# SilovaCast.net
KiCad netlist of a schematic drawn in EAGLE
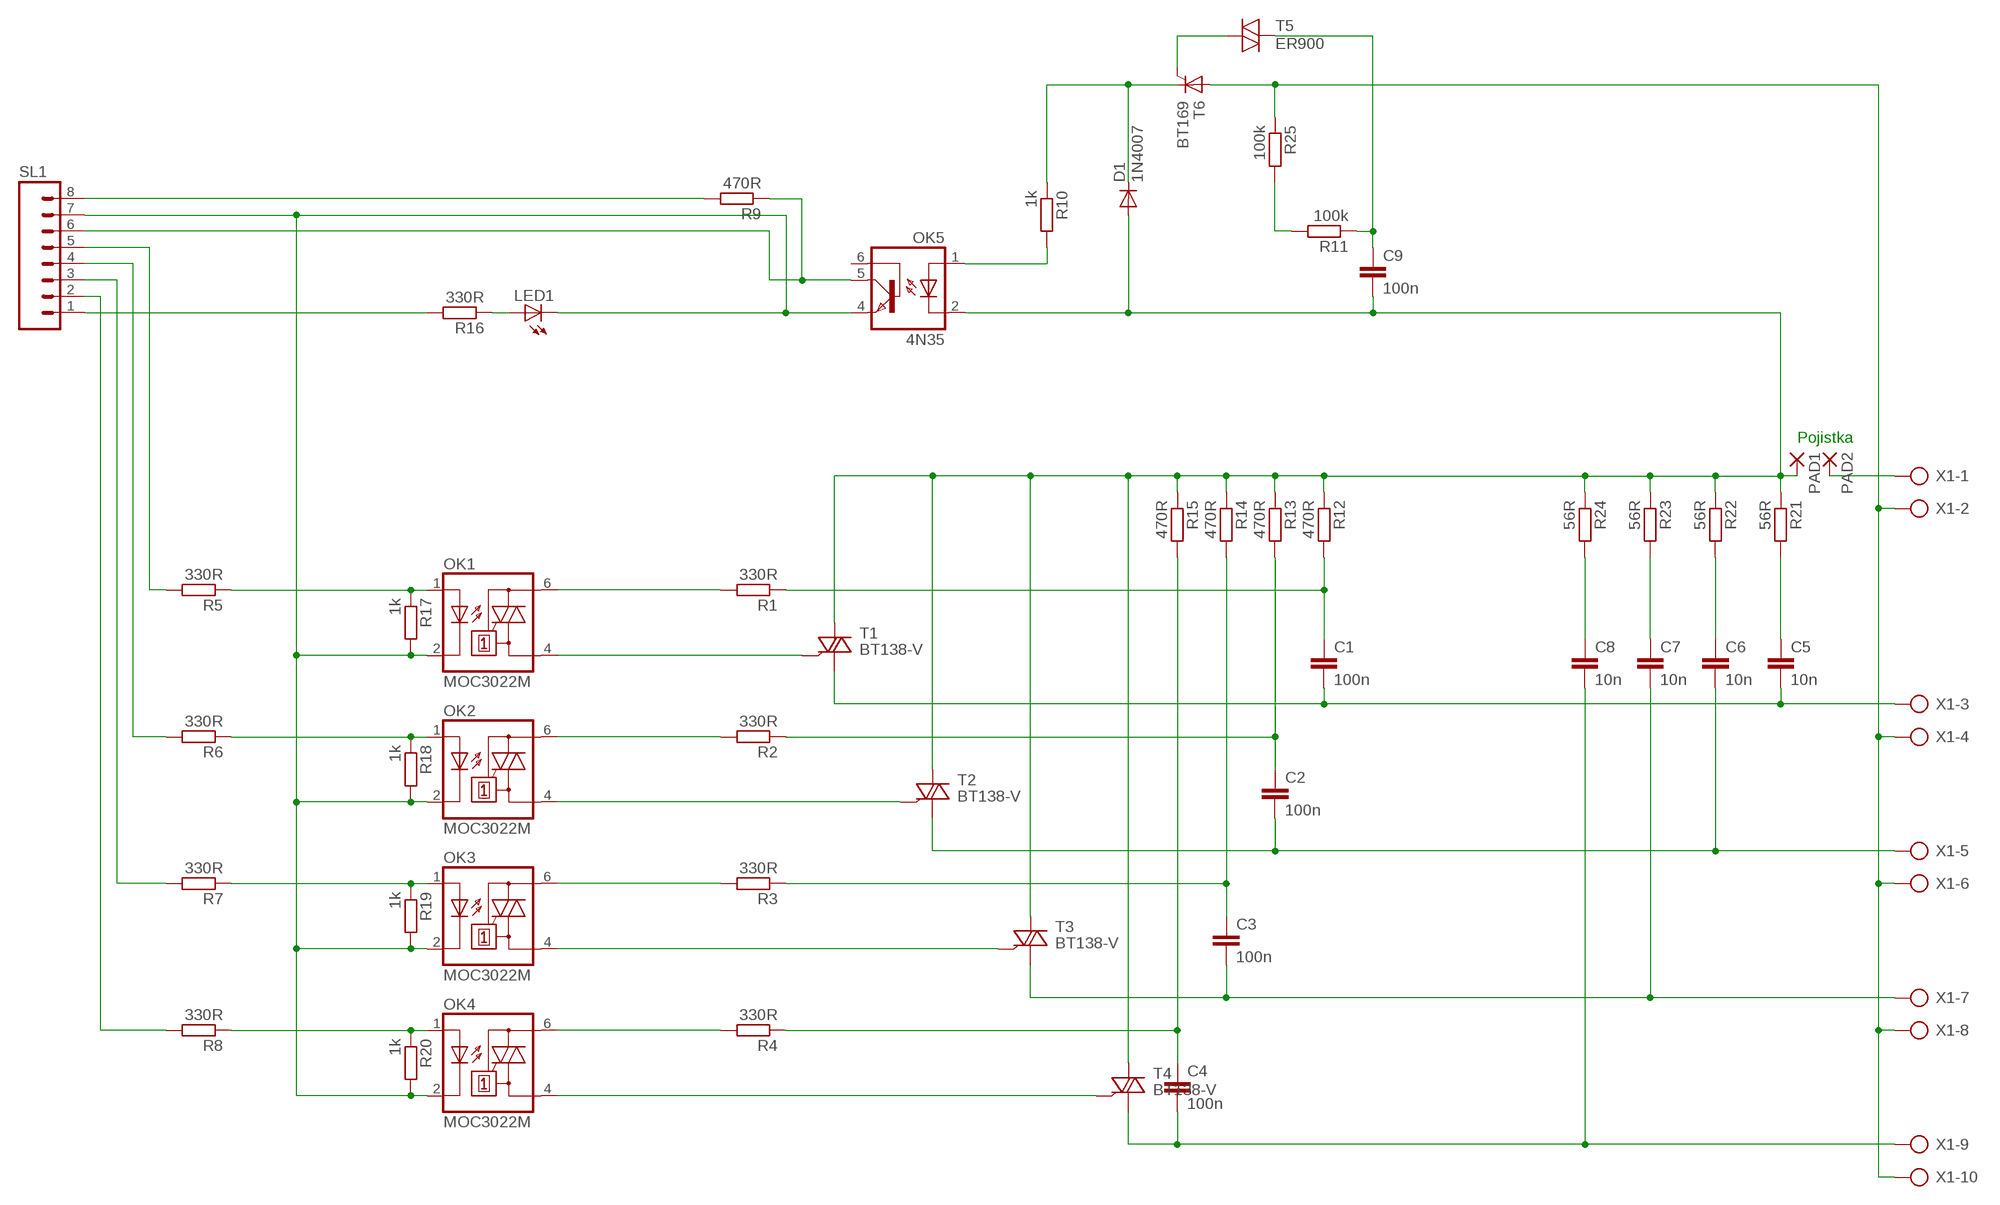
[diagram p0: schematic, sheet 1]

(export (version "E")
  (design (tool "Eeschema 10.0.6"))
  (components
    (comp (ref "C1")
      (value "100n")
      (footprint "eagle-import:C7.5B6")
      (libsource (lib "eagle-import") (part "C7.5/6"))
    )
    (comp (ref "C2")
      (value "100n")
      (footprint "eagle-import:C7.5B6")
      (libsource (lib "eagle-import") (part "C7.5/6"))
    )
    (comp (ref "C3")
      (value "100n")
      (footprint "eagle-import:C7.5B6")
      (libsource (lib "eagle-import") (part "C7.5/6"))
    )
    (comp (ref "C4")
      (value "100n")
      (footprint "eagle-import:C7.5B6")
      (libsource (lib "eagle-import") (part "C7.5/6"))
    )
    (comp (ref "C5")
      (value "10n")
      (footprint "eagle-import:C7.5B6")
      (libsource (lib "eagle-import") (part "C7.5/6"))
    )
    (comp (ref "C6")
      (value "10n")
      (footprint "eagle-import:C7.5B6")
      (libsource (lib "eagle-import") (part "C7.5/6"))
    )
    (comp (ref "C7")
      (value "10n")
      (footprint "eagle-import:C7.5B6")
      (libsource (lib "eagle-import") (part "C7.5/6"))
    )
    (comp (ref "C8")
      (value "10n")
      (footprint "eagle-import:C7.5B6")
      (libsource (lib "eagle-import") (part "C7.5/6"))
    )
    (comp (ref "C9")
      (value "100n")
      (footprint "eagle-import:C7.5B6")
      (libsource (lib "eagle-import") (part "C7.5/6"))
    )
    (comp (ref "D1")
      (value "1N4007")
      (footprint "eagle-import:DO41-10")
      (libsource (lib "eagle-import") (part "1N4004"))
    )
    (comp (ref "LED1")
      (value "LED5MM")
      (footprint "eagle-import:LED5MM")
      (libsource (lib "eagle-import") (part "LED5MM"))
    )
    (comp (ref "OK1")
      (value "MOC3022M")
      (footprint "eagle-import:DIL06")
      (fields (field (name "MF") "FAIRCHILD SEMICONDUCTOR") (field (name "MPN") "MOC3022-M"))
      (libsource (lib "eagle-import") (part "MOC30M22"))
    )
    (comp (ref "OK2")
      (value "MOC3022M")
      (footprint "eagle-import:DIL06")
      (fields (field (name "MF") "FAIRCHILD SEMICONDUCTOR") (field (name "MPN") "MOC3022-M"))
      (libsource (lib "eagle-import") (part "MOC30M22"))
    )
    (comp (ref "OK3")
      (value "MOC3022M")
      (footprint "eagle-import:DIL06")
      (fields (field (name "MF") "FAIRCHILD SEMICONDUCTOR") (field (name "MPN") "MOC3022-M"))
      (libsource (lib "eagle-import") (part "MOC30M22"))
    )
    (comp (ref "OK4")
      (value "MOC3022M")
      (footprint "eagle-import:DIL06")
      (fields (field (name "MF") "FAIRCHILD SEMICONDUCTOR") (field (name "MPN") "MOC3022-M"))
      (libsource (lib "eagle-import") (part "MOC30M22"))
    )
    (comp (ref "OK5")
      (value "4N35")
      (footprint "eagle-import:DIL06")
      (fields (field (name "MF") "FAIRCHILD SEMICONDUCTOR"))
      (libsource (lib "eagle-import") (part "4N35"))
    )
    (comp (ref "PAD1")
      (value "3,17/1,3")
      (footprint "eagle-import:3,17_1,3")
      (libsource (lib "eagle-import") (part "3,17/1,3"))
    )
    (comp (ref "PAD2")
      (value "3,17/1,3")
      (footprint "eagle-import:3,17_1,3")
      (libsource (lib "eagle-import") (part "3,17/1,3"))
    )
    (comp (ref "R1")
      (value "330R")
      (footprint "eagle-import:0207_12")
      (libsource (lib "eagle-import") (part "R-EU_0207/12"))
    )
    (comp (ref "R2")
      (value "330R")
      (footprint "eagle-import:0207_12")
      (libsource (lib "eagle-import") (part "R-EU_0207/12"))
    )
    (comp (ref "R3")
      (value "330R")
      (footprint "eagle-import:0207_12")
      (libsource (lib "eagle-import") (part "R-EU_0207/12"))
    )
    (comp (ref "R4")
      (value "330R")
      (footprint "eagle-import:0207_12")
      (libsource (lib "eagle-import") (part "R-EU_0207/12"))
    )
    (comp (ref "R5")
      (value "330R")
      (footprint "eagle-import:R0805")
      (libsource (lib "eagle-import") (part "R-EU_R0805"))
    )
    (comp (ref "R6")
      (value "330R")
      (footprint "eagle-import:R0805")
      (libsource (lib "eagle-import") (part "R-EU_R0805"))
    )
    (comp (ref "R7")
      (value "330R")
      (footprint "eagle-import:R0805")
      (libsource (lib "eagle-import") (part "R-EU_R0805"))
    )
    (comp (ref "R8")
      (value "330R")
      (footprint "eagle-import:R0805")
      (libsource (lib "eagle-import") (part "R-EU_R0805"))
    )
    (comp (ref "R9")
      (value "470R")
      (footprint "eagle-import:0207_12")
      (libsource (lib "eagle-import") (part "R-EU_0207/12"))
    )
    (comp (ref "R10")
      (value "1k")
      (footprint "eagle-import:0207_12")
      (libsource (lib "eagle-import") (part "R-EU_0207/12"))
    )
    (comp (ref "R11")
      (value "100k")
      (footprint "eagle-import:0207_12")
      (libsource (lib "eagle-import") (part "R-EU_0207/12"))
    )
    (comp (ref "R12")
      (value "470R")
      (footprint "eagle-import:0207_12")
      (libsource (lib "eagle-import") (part "R-EU_0207/12"))
    )
    (comp (ref "R13")
      (value "470R")
      (footprint "eagle-import:0207_12")
      (libsource (lib "eagle-import") (part "R-EU_0207/12"))
    )
    (comp (ref "R14")
      (value "470R")
      (footprint "eagle-import:0207_12")
      (libsource (lib "eagle-import") (part "R-EU_0207/12"))
    )
    (comp (ref "R15")
      (value "470R")
      (footprint "eagle-import:0207_12")
      (libsource (lib "eagle-import") (part "R-EU_0207/12"))
    )
    (comp (ref "R16")
      (value "330R")
      (footprint "eagle-import:0207_12")
      (libsource (lib "eagle-import") (part "R-EU_0207/12"))
    )
    (comp (ref "R17")
      (value "1k")
      (footprint "eagle-import:R0805")
      (libsource (lib "eagle-import") (part "R-EU_R0805"))
    )
    (comp (ref "R18")
      (value "1k")
      (footprint "eagle-import:R0805")
      (libsource (lib "eagle-import") (part "R-EU_R0805"))
    )
    (comp (ref "R19")
      (value "1k")
      (footprint "eagle-import:R0805")
      (libsource (lib "eagle-import") (part "R-EU_R0805"))
    )
    (comp (ref "R20")
      (value "1k")
      (footprint "eagle-import:R0805")
      (libsource (lib "eagle-import") (part "R-EU_R0805"))
    )
    (comp (ref "R21")
      (value "56R")
      (footprint "eagle-import:0411_15")
      (libsource (lib "eagle-import") (part "R-EU_0411/15"))
    )
    (comp (ref "R22")
      (value "56R")
      (footprint "eagle-import:0411_15")
      (libsource (lib "eagle-import") (part "R-EU_0411/15"))
    )
    (comp (ref "R23")
      (value "56R")
      (footprint "eagle-import:0411_15")
      (libsource (lib "eagle-import") (part "R-EU_0411/15"))
    )
    (comp (ref "R24")
      (value "56R")
      (footprint "eagle-import:0411_15")
      (libsource (lib "eagle-import") (part "R-EU_0411/15"))
    )
    (comp (ref "R25")
      (value "100k")
      (footprint "eagle-import:0207_12")
      (libsource (lib "eagle-import") (part "R-EU_0207/12"))
    )
    (comp (ref "SL1")
      (value "M08")
      (footprint "eagle-import:08P")
      (libsource (lib "eagle-import") (part "M08"))
    )
    (comp (ref "T1")
      (value "BT138-V")
      (footprint "eagle-import:TO220BV")
      (libsource (lib "eagle-import") (part "BT138-V"))
    )
    (comp (ref "T2")
      (value "BT138-V")
      (footprint "eagle-import:TO220BV")
      (libsource (lib "eagle-import") (part "BT138-V"))
    )
    (comp (ref "T3")
      (value "BT138-V")
      (footprint "eagle-import:TO220BV")
      (libsource (lib "eagle-import") (part "BT138-V"))
    )
    (comp (ref "T4")
      (value "BT138-V")
      (footprint "eagle-import:TO220BV")
      (libsource (lib "eagle-import") (part "BT138-V"))
    )
    (comp (ref "T5")
      (value "ER900")
      (footprint "eagle-import:ER900")
      (libsource (lib "eagle-import") (part "ER900"))
    )
    (comp (ref "T6")
      (value "BT169")
      (footprint "eagle-import:TO92-2")
      (libsource (lib "eagle-import") (part "BT169"))
    )
    (comp (ref "X1")
      (value "AK300/10")
      (footprint "eagle-import:AK300_10")
      (libsource (lib "eagle-import") (part "AK300/10"))
    )
  )
  (nets
    (net (code "1") (name "Net-(C1-Pad1)") (class "Default")
      (node (ref "C1") (pin "1") (pinfunction "1_1") (pintype "passive"))
      (node (ref "R1") (pin "1") (pinfunction "1_1") (pintype "passive"))
      (node (ref "R12") (pin "2") (pinfunction "2_2") (pintype "passive"))
    )
    (net (code "2") (name "Net-(C2-Pad1)") (class "Default")
      (node (ref "C2") (pin "1") (pinfunction "1_1") (pintype "passive"))
      (node (ref "R13") (pin "2") (pinfunction "2_2") (pintype "passive"))
      (node (ref "R2") (pin "1") (pinfunction "1_1") (pintype "passive"))
    )
    (net (code "3") (name "Net-(C3-Pad1)") (class "Default")
      (node (ref "C3") (pin "1") (pinfunction "1_1") (pintype "passive"))
      (node (ref "R14") (pin "2") (pinfunction "2_2") (pintype "passive"))
      (node (ref "R3") (pin "1") (pinfunction "1_1") (pintype "passive"))
    )
    (net (code "4") (name "Net-(C4-Pad1)") (class "Default")
      (node (ref "C4") (pin "1") (pinfunction "1_1") (pintype "passive"))
      (node (ref "R15") (pin "2") (pinfunction "2_2") (pintype "passive"))
      (node (ref "R4") (pin "1") (pinfunction "1_1") (pintype "passive"))
    )
    (net (code "5") (name "Net-(C5-Pad1)") (class "Default")
      (node (ref "C5") (pin "1") (pinfunction "1_1") (pintype "passive"))
      (node (ref "R21") (pin "2") (pinfunction "2_2") (pintype "passive"))
    )
    (net (code "6") (name "Net-(C6-Pad1)") (class "Default")
      (node (ref "C6") (pin "1") (pinfunction "1_1") (pintype "passive"))
      (node (ref "R22") (pin "2") (pinfunction "2_2") (pintype "passive"))
    )
    (net (code "7") (name "Net-(C7-Pad1)") (class "Default")
      (node (ref "C7") (pin "1") (pinfunction "1_1") (pintype "passive"))
      (node (ref "R23") (pin "2") (pinfunction "2_2") (pintype "passive"))
    )
    (net (code "8") (name "Net-(C8-Pad1)") (class "Default")
      (node (ref "C8") (pin "1") (pinfunction "1_1") (pintype "passive"))
      (node (ref "R24") (pin "2") (pinfunction "2_2") (pintype "passive"))
    )
    (net (code "9") (name "Net-(C9-Pad1)") (class "Default")
      (node (ref "C9") (pin "1") (pinfunction "1_1") (pintype "passive"))
      (node (ref "R11") (pin "1") (pinfunction "1_1") (pintype "passive"))
      (node (ref "T5") (pin "2") (pinfunction "2_2") (pintype "passive"))
    )
    (net (code "10") (name "Net-(D1-PadC)") (class "Default")
      (node (ref "D1") (pin "C") (pinfunction "C_C") (pintype "passive"))
      (node (ref "R10") (pin "1") (pinfunction "1_1") (pintype "passive"))
      (node (ref "T6") (pin "C") (pinfunction "C_C") (pintype "passive"))
    )
    (net (code "11") (name "Net-(LED1-C)") (class "Default")
      (node (ref "LED1") (pin "K") (pinfunction "C_K") (pintype "passive"))
      (node (ref "OK1") (pin "2") (pinfunction "C_2") (pintype "passive"))
      (node (ref "OK2") (pin "2") (pinfunction "C_2") (pintype "passive"))
      (node (ref "OK3") (pin "2") (pinfunction "C_2") (pintype "passive"))
      (node (ref "OK4") (pin "2") (pinfunction "C_2") (pintype "passive"))
      (node (ref "OK5") (pin "4") (pinfunction "EMI_4") (pintype "passive"))
      (node (ref "R17") (pin "2") (pinfunction "2_2") (pintype "passive"))
      (node (ref "R18") (pin "2") (pinfunction "2_2") (pintype "passive"))
      (node (ref "R19") (pin "2") (pinfunction "2_2") (pintype "passive"))
      (node (ref "R20") (pin "2") (pinfunction "2_2") (pintype "passive"))
      (node (ref "SL1") (pin "7") (pinfunction "7_7") (pintype "passive"))
    )
    (net (code "12") (name "Net-(LED1-PadA)") (class "Default")
      (node (ref "LED1") (pin "A") (pinfunction "A_A") (pintype "passive"))
      (node (ref "R16") (pin "1") (pinfunction "1_1") (pintype "passive"))
    )
    (net (code "13") (name "Net-(OK1-A)") (class "Default")
      (node (ref "OK1") (pin "1") (pinfunction "A_1") (pintype "passive"))
      (node (ref "R17") (pin "1") (pinfunction "1_1") (pintype "passive"))
      (node (ref "R5") (pin "1") (pinfunction "1_1") (pintype "passive"))
    )
    (net (code "14") (name "Net-(OK1-A1)") (class "Default")
      (node (ref "OK1") (pin "4") (pinfunction "A1_4") (pintype "passive"))
      (node (ref "T1") (pin "G") (pinfunction "G_G") (pintype "passive"))
    )
    (net (code "15") (name "Net-(OK1-A2)") (class "Default")
      (node (ref "OK1") (pin "6") (pinfunction "A2_6") (pintype "passive"))
      (node (ref "R1") (pin "2") (pinfunction "2_2") (pintype "passive"))
    )
    (net (code "16") (name "Net-(OK2-A)") (class "Default")
      (node (ref "OK2") (pin "1") (pinfunction "A_1") (pintype "passive"))
      (node (ref "R18") (pin "1") (pinfunction "1_1") (pintype "passive"))
      (node (ref "R6") (pin "1") (pinfunction "1_1") (pintype "passive"))
    )
    (net (code "17") (name "Net-(OK2-A1)") (class "Default")
      (node (ref "OK2") (pin "4") (pinfunction "A1_4") (pintype "passive"))
      (node (ref "T2") (pin "G") (pinfunction "G_G") (pintype "passive"))
    )
    (net (code "18") (name "Net-(OK2-A2)") (class "Default")
      (node (ref "OK2") (pin "6") (pinfunction "A2_6") (pintype "passive"))
      (node (ref "R2") (pin "2") (pinfunction "2_2") (pintype "passive"))
    )
    (net (code "19") (name "Net-(OK3-A)") (class "Default")
      (node (ref "OK3") (pin "1") (pinfunction "A_1") (pintype "passive"))
      (node (ref "R19") (pin "1") (pinfunction "1_1") (pintype "passive"))
      (node (ref "R7") (pin "1") (pinfunction "1_1") (pintype "passive"))
    )
    (net (code "20") (name "Net-(OK3-A1)") (class "Default")
      (node (ref "OK3") (pin "4") (pinfunction "A1_4") (pintype "passive"))
      (node (ref "T3") (pin "G") (pinfunction "G_G") (pintype "passive"))
    )
    (net (code "21") (name "Net-(OK3-A2)") (class "Default")
      (node (ref "OK3") (pin "6") (pinfunction "A2_6") (pintype "passive"))
      (node (ref "R3") (pin "2") (pinfunction "2_2") (pintype "passive"))
    )
    (net (code "22") (name "Net-(OK4-A)") (class "Default")
      (node (ref "OK4") (pin "1") (pinfunction "A_1") (pintype "passive"))
      (node (ref "R20") (pin "1") (pinfunction "1_1") (pintype "passive"))
      (node (ref "R8") (pin "1") (pinfunction "1_1") (pintype "passive"))
    )
    (net (code "23") (name "Net-(OK4-A1)") (class "Default")
      (node (ref "OK4") (pin "4") (pinfunction "A1_4") (pintype "passive"))
      (node (ref "T4") (pin "G") (pinfunction "G_G") (pintype "passive"))
    )
    (net (code "24") (name "Net-(OK4-A2)") (class "Default")
      (node (ref "OK4") (pin "6") (pinfunction "A2_6") (pintype "passive"))
      (node (ref "R4") (pin "2") (pinfunction "2_2") (pintype "passive"))
    )
    (net (code "25") (name "Net-(OK5-A)") (class "Default")
      (node (ref "OK5") (pin "1") (pinfunction "A_1") (pintype "passive"))
      (node (ref "R10") (pin "2") (pinfunction "2_2") (pintype "passive"))
    )
    (net (code "26") (name "Net-(OK5-C)") (class "Default")
      (node (ref "C9") (pin "2") (pinfunction "2_2") (pintype "passive"))
      (node (ref "D1") (pin "A") (pinfunction "A_A") (pintype "passive"))
      (node (ref "OK5") (pin "2") (pinfunction "C_2") (pintype "passive"))
      (node (ref "PAD1") (pin "1") (pinfunction "P_1") (pintype "passive"))
      (node (ref "R12") (pin "1") (pinfunction "1_1") (pintype "passive"))
      (node (ref "R13") (pin "1") (pinfunction "1_1") (pintype "passive"))
      (node (ref "R14") (pin "1") (pinfunction "1_1") (pintype "passive"))
      (node (ref "R15") (pin "1") (pinfunction "1_1") (pintype "passive"))
      (node (ref "R21") (pin "1") (pinfunction "1_1") (pintype "passive"))
      (node (ref "R22") (pin "1") (pinfunction "1_1") (pintype "passive"))
      (node (ref "R23") (pin "1") (pinfunction "1_1") (pintype "passive"))
      (node (ref "R24") (pin "1") (pinfunction "1_1") (pintype "passive"))
      (node (ref "T1") (pin "T2") (pinfunction "A2_T2") (pintype "passive"))
      (node (ref "T2") (pin "T2") (pinfunction "A2_T2") (pintype "passive"))
      (node (ref "T3") (pin "T2") (pinfunction "A2_T2") (pintype "passive"))
      (node (ref "T4") (pin "T2") (pinfunction "A2_T2") (pintype "passive"))
    )
    (net (code "27") (name "Net-(OK5-COL)") (class "Default")
      (node (ref "OK5") (pin "5") (pinfunction "COL_5") (pintype "passive"))
      (node (ref "R9") (pin "1") (pinfunction "1_1") (pintype "passive"))
      (node (ref "SL1") (pin "6") (pinfunction "6_6") (pintype "passive"))
    )
    (net (code "28") (name "Net-(PAD2-P)") (class "Default")
      (node (ref "PAD2") (pin "1") (pinfunction "P_1") (pintype "passive"))
      (node (ref "X1") (pin "1") (pinfunction "KL_1") (pintype "passive"))
    )
    (net (code "29") (name "Net-(R5-Pad2)") (class "Default")
      (node (ref "R5") (pin "2") (pinfunction "2_2") (pintype "passive"))
      (node (ref "SL1") (pin "5") (pinfunction "5_5") (pintype "passive"))
    )
    (net (code "30") (name "Net-(R6-Pad2)") (class "Default")
      (node (ref "R6") (pin "2") (pinfunction "2_2") (pintype "passive"))
      (node (ref "SL1") (pin "4") (pinfunction "4_4") (pintype "passive"))
    )
    (net (code "31") (name "Net-(R7-Pad2)") (class "Default")
      (node (ref "R7") (pin "2") (pinfunction "2_2") (pintype "passive"))
      (node (ref "SL1") (pin "3") (pinfunction "3_3") (pintype "passive"))
    )
    (net (code "32") (name "Net-(R8-Pad2)") (class "Default")
      (node (ref "R8") (pin "2") (pinfunction "2_2") (pintype "passive"))
      (node (ref "SL1") (pin "2") (pinfunction "2_2") (pintype "passive"))
    )
    (net (code "33") (name "Net-(R9-Pad2)") (class "Default")
      (node (ref "R9") (pin "2") (pinfunction "2_2") (pintype "passive"))
      (node (ref "SL1") (pin "8") (pinfunction "8_8") (pintype "passive"))
    )
    (net (code "34") (name "Net-(R11-Pad2)") (class "Default")
      (node (ref "R11") (pin "2") (pinfunction "2_2") (pintype "passive"))
      (node (ref "R25") (pin "2") (pinfunction "2_2") (pintype "passive"))
    )
    (net (code "35") (name "Net-(R16-Pad2)") (class "Default")
      (node (ref "R16") (pin "2") (pinfunction "2_2") (pintype "passive"))
      (node (ref "SL1") (pin "1") (pinfunction "1_1") (pintype "passive"))
    )
    (net (code "36") (name "Net-(T1-A1)") (class "Default")
      (node (ref "C1") (pin "2") (pinfunction "2_2") (pintype "passive"))
      (node (ref "C5") (pin "2") (pinfunction "2_2") (pintype "passive"))
      (node (ref "T1") (pin "T1") (pinfunction "A1_T1") (pintype "passive"))
      (node (ref "X1") (pin "3") (pinfunction "KL_3") (pintype "passive"))
    )
    (net (code "37") (name "Net-(T2-A1)") (class "Default")
      (node (ref "C2") (pin "2") (pinfunction "2_2") (pintype "passive"))
      (node (ref "C6") (pin "2") (pinfunction "2_2") (pintype "passive"))
      (node (ref "T2") (pin "T1") (pinfunction "A1_T1") (pintype "passive"))
      (node (ref "X1") (pin "5") (pinfunction "KL_5") (pintype "passive"))
    )
    (net (code "38") (name "Net-(T3-A1)") (class "Default")
      (node (ref "C3") (pin "2") (pinfunction "2_2") (pintype "passive"))
      (node (ref "C7") (pin "2") (pinfunction "2_2") (pintype "passive"))
      (node (ref "T3") (pin "T1") (pinfunction "A1_T1") (pintype "passive"))
      (node (ref "X1") (pin "7") (pinfunction "KL_7") (pintype "passive"))
    )
    (net (code "39") (name "Net-(T4-A1)") (class "Default")
      (node (ref "C4") (pin "2") (pinfunction "2_2") (pintype "passive"))
      (node (ref "C8") (pin "2") (pinfunction "2_2") (pintype "passive"))
      (node (ref "T4") (pin "T1") (pinfunction "A1_T1") (pintype "passive"))
      (node (ref "X1") (pin "9") (pinfunction "KL_9") (pintype "passive"))
    )
    (net (code "40") (name "Net-(T5-Pad1)") (class "Default")
      (node (ref "T5") (pin "1") (pinfunction "1_1") (pintype "passive"))
      (node (ref "T6") (pin "G") (pinfunction "G_G") (pintype "passive"))
    )
    (net (code "41") (name "Net-(X1B-KL)") (class "Default")
      (node (ref "R25") (pin "1") (pinfunction "1_1") (pintype "passive"))
      (node (ref "T6") (pin "A") (pinfunction "A_A") (pintype "passive"))
      (node (ref "X1") (pin "10") (pinfunction "KL_10") (pintype "passive"))
      (node (ref "X1") (pin "2") (pinfunction "KL_2") (pintype "passive"))
      (node (ref "X1") (pin "4") (pinfunction "KL_4") (pintype "passive"))
      (node (ref "X1") (pin "6") (pinfunction "KL_6") (pintype "passive"))
      (node (ref "X1") (pin "8") (pinfunction "KL_8") (pintype "passive"))
    )
    (net (code "42") (name "unconnected-(OK5-BAS-Pad6)") (class "Default")
      (node (ref "OK5") (pin "6") (pinfunction "BAS_6") (pintype "passive"))
    )
  )
)
